# CoffeeHeater.net
KiCad netlist of a schematic drawn in EAGLE
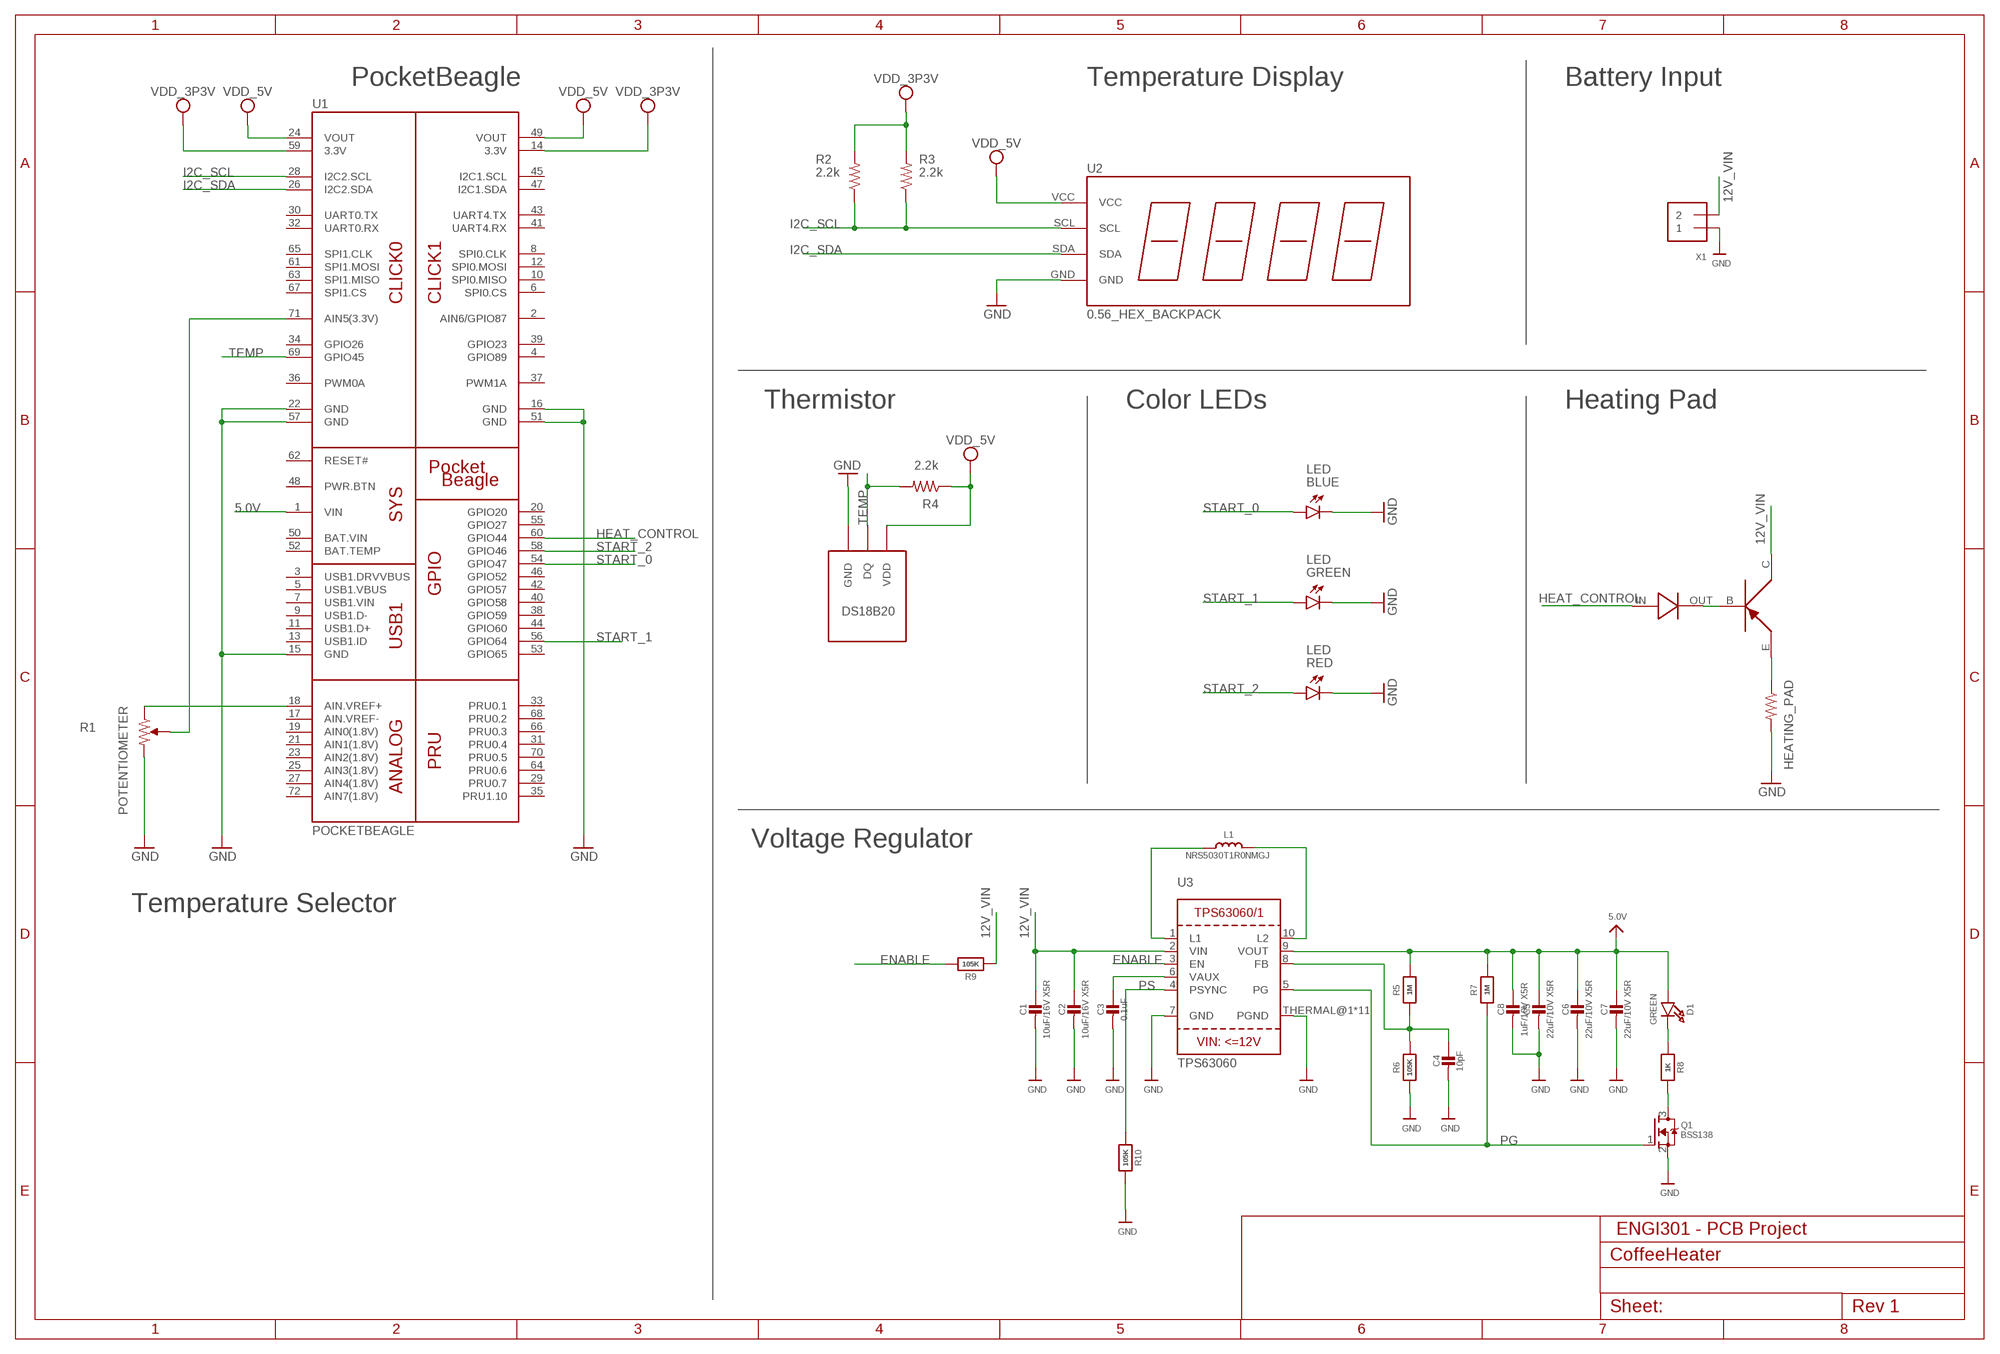
[diagram p0: schematic, sheet 1]

(export (version "E")
  (design (tool "Eeschema 10.0.6"))
  (components
    (comp (ref "BLUE")
      (value "LED")
      (footprint "eagle-import:EIA-STD")
      (libsource (lib "eagle-import") (part "LED"))
    )
    (comp (ref "C1")
      (value "10uF/16V X5R")
      (footprint "eagle-import:0805-NO")
      (libsource (lib "eagle-import") (part "CAP_CERAMIC0805-NOOUTLINE"))
    )
    (comp (ref "C2")
      (value "10uF/16V X5R")
      (footprint "eagle-import:0805-NO")
      (libsource (lib "eagle-import") (part "CAP_CERAMIC0805-NOOUTLINE"))
    )
    (comp (ref "C3")
      (value "0.1uF")
      (footprint "eagle-import:0805-NO")
      (libsource (lib "eagle-import") (part "CAP_CERAMIC0805-NOOUTLINE"))
    )
    (comp (ref "C4")
      (value "10pF")
      (footprint "eagle-import:0805-NO")
      (libsource (lib "eagle-import") (part "CAP_CERAMIC0805-NOOUTLINE"))
    )
    (comp (ref "C5")
      (value "22uF/10V X5R")
      (footprint "eagle-import:0805-NO")
      (libsource (lib "eagle-import") (part "CAP_CERAMIC0805-NOOUTLINE"))
    )
    (comp (ref "C6")
      (value "22uF/10V X5R")
      (footprint "eagle-import:0805-NO")
      (libsource (lib "eagle-import") (part "CAP_CERAMIC0805-NOOUTLINE"))
    )
    (comp (ref "C7")
      (value "22uF/10V X5R")
      (footprint "eagle-import:0805-NO")
      (libsource (lib "eagle-import") (part "CAP_CERAMIC0805-NOOUTLINE"))
    )
    (comp (ref "C8")
      (value "1uF/10V X5R")
      (footprint "eagle-import:0805-NO")
      (libsource (lib "eagle-import") (part "CAP_CERAMIC0805-NOOUTLINE"))
    )
    (comp (ref "D1")
      (value "GREEN")
      (footprint "eagle-import:CHIPLED_0805_NOOUTLINE")
      (libsource (lib "eagle-import") (part "LED0805_NOOUTLINE"))
    )
    (comp (ref "GREEN")
      (value "LED")
      (footprint "eagle-import:EIA-STD")
      (libsource (lib "eagle-import") (part "LED"))
    )
    (comp (ref "L1")
      (value "NRS5030T1R0NMGJ")
      (footprint "eagle-import:INDUCTOR_5X5MM_TDK_VLC5045")
      (libsource (lib "eagle-import") (part "INDUCTORTDK_VLC5045"))
    )
    (comp (ref "Q1")
      (value "BSS138")
      (footprint "eagle-import:SOT23-WIDE")
      (libsource (lib "eagle-import") (part "MOSFET-NWIDE"))
    )
    (comp (ref "R1")
      (value "POTENTIOMETER")
      (footprint "eagle-import:POT-PO90S")
      (libsource (lib "eagle-import") (part "POTENTIOMETER"))
    )
    (comp (ref "R2")
      (value "2.2k")
      (footprint "eagle-import:R0603")
      (libsource (lib "eagle-import") (part "R_R0603"))
    )
    (comp (ref "R3")
      (value "2.2k")
      (footprint "eagle-import:R0603")
      (libsource (lib "eagle-import") (part "R_R0603"))
    )
    (comp (ref "R4")
      (value "2.2k")
      (footprint "eagle-import:R0603")
      (libsource (lib "eagle-import") (part "R_R0603"))
    )
    (comp (ref "R5")
      (value "1M")
      (footprint "eagle-import:0805-NO")
      (libsource (lib "eagle-import") (part "RESISTOR0805_NOOUTLINE"))
    )
    (comp (ref "R6")
      (value "105K")
      (footprint "eagle-import:0805-NO")
      (libsource (lib "eagle-import") (part "RESISTOR0805_NOOUTLINE"))
    )
    (comp (ref "R7")
      (value "1M")
      (footprint "eagle-import:0805-NO")
      (libsource (lib "eagle-import") (part "RESISTOR0805_NOOUTLINE"))
    )
    (comp (ref "R8")
      (value "1K")
      (footprint "eagle-import:0805-NO")
      (libsource (lib "eagle-import") (part "RESISTOR0805_NOOUTLINE"))
    )
    (comp (ref "R9")
      (value "105K")
      (footprint "eagle-import:0805-NO")
      (libsource (lib "eagle-import") (part "RESISTOR0805_NOOUTLINE"))
    )
    (comp (ref "R10")
      (value "105K")
      (footprint "eagle-import:0805-NO")
      (libsource (lib "eagle-import") (part "RESISTOR0805_NOOUTLINE"))
    )
    (comp (ref "RED")
      (value "LED")
      (footprint "eagle-import:EIA-STD")
      (libsource (lib "eagle-import") (part "LED"))
    )
    (comp (ref "U$1")
      (value "DS18B20_TEMP_SENSOR")
      (footprint "eagle-import:DS18B20_TEMP_SENSOR")
      (libsource (lib "eagle-import") (part "DS18B20_TEMP_SENSOR"))
    )
    (comp (ref "U$2")
      (value "TIP32C_TRANSISTOR")
      (footprint "eagle-import:TIP32C_TRANSISTOR")
      (libsource (lib "eagle-import") (part "TIP32C_TRANSISTOR"))
    )
    (comp (ref "U$3")
      (value "DIODE")
      (footprint "eagle-import:DIODE")
      (libsource (lib "eagle-import") (part "DIODE"))
    )
    (comp (ref "U$4")
      (value "HEATING_PAD")
      (footprint "eagle-import:HEATING_PAD")
      (libsource (lib "eagle-import") (part "HEATING_PAD"))
    )
    (comp (ref "U1")
      (value "POCKETBEAGLE")
      (footprint "eagle-import:POCKETBEAGLE")
      (libsource (lib "eagle-import") (part "POCKETBEAGLE"))
    )
    (comp (ref "U2")
      (value "0.56_HEX_BACKPACK")
      (footprint "eagle-import:0.56_HEX_BACKPACK")
      (libsource (lib "eagle-import") (part "0.56_HEX_BACKPACK"))
    )
    (comp (ref "U3")
      (value "TPS63060")
      (footprint "eagle-import:PWSON-N10")
      (libsource (lib "eagle-import") (part "VREG_TPS63060/1"))
    )
    (comp (ref "X1")
      (value "TERMBLOCK_1X2")
      (footprint "eagle-import:TERMBLOCK_1X2-3.5MM")
      (libsource (lib "eagle-import") (part "TERMBLOCK_1X2"))
    )
  )
  (nets
    (net (code "1") (name "/12V_VIN") (class "Default")
      (node (ref "C1") (pin "1") (pinfunction "1_1") (pintype "passive"))
      (node (ref "C2") (pin "1") (pinfunction "1_1") (pintype "passive"))
      (node (ref "R9") (pin "1") (pinfunction "1_1") (pintype "passive"))
      (node (ref "U$2") (pin "C") (pinfunction "C_C") (pintype "bidirectional"))
      (node (ref "U3") (pin "2") (pinfunction "VIN_2") (pintype "power_in"))
      (node (ref "X1") (pin "2") (pinfunction "2_2") (pintype "passive"))
    )
    (net (code "2") (name "/BAT.VIN") (class "Default")
      (node (ref "U1") (pin "50") (pinfunction "BAT.VIN_50") (pintype "power_in"))
    )
    (net (code "3") (name "/ENABLE") (class "Default")
      (node (ref "R9") (pin "2") (pinfunction "2_2") (pintype "passive"))
      (node (ref "U3") (pin "3") (pinfunction "EN_3") (pintype "input"))
    )
    (net (code "4") (name "/HEAT_CONTROL") (class "Default")
      (node (ref "U$3") (pin "IN") (pinfunction "IN_IN") (pintype "bidirectional"))
      (node (ref "U1") (pin "60") (pinfunction "GPIO44_60") (pintype "bidirectional"))
    )
    (net (code "5") (name "/I2C_SCL") (class "Default")
      (node (ref "R2") (pin "1") (pinfunction "1_1") (pintype "passive"))
      (node (ref "R3") (pin "1") (pinfunction "1_1") (pintype "passive"))
      (node (ref "U1") (pin "28") (pinfunction "I2C2.SCL_28") (pintype "bidirectional"))
      (node (ref "U2") (pin "SCL") (pinfunction "SCL_SCL") (pintype "bidirectional"))
    )
    (net (code "6") (name "/I2C_SDA") (class "Default")
      (node (ref "U1") (pin "26") (pinfunction "I2C2.SDA_26") (pintype "bidirectional"))
      (node (ref "U2") (pin "SDA") (pinfunction "SDA_SDA") (pintype "bidirectional"))
    )
    (net (code "7") (name "/PG") (class "Default")
      (node (ref "Q1") (pin "1") (pinfunction "G_1") (pintype "bidirectional"))
      (node (ref "R7") (pin "1") (pinfunction "1_1") (pintype "passive"))
      (node (ref "U3") (pin "5") (pinfunction "PG_5") (pintype "open_collector"))
    )
    (net (code "8") (name "/PS") (class "Default")
      (node (ref "R10") (pin "1") (pinfunction "1_1") (pintype "passive"))
      (node (ref "U3") (pin "4") (pinfunction "PSYNC_4") (pintype "input"))
    )
    (net (code "9") (name "/START_0") (class "Default")
      (node (ref "BLUE") (pin "P$1") (pinfunction "A_P$1") (pintype "passive"))
      (node (ref "U1") (pin "54") (pinfunction "GPIO47_54") (pintype "bidirectional"))
    )
    (net (code "10") (name "/START_1") (class "Default")
      (node (ref "GREEN") (pin "P$1") (pinfunction "A_P$1") (pintype "passive"))
      (node (ref "U1") (pin "56") (pinfunction "GPIO64_56") (pintype "bidirectional"))
    )
    (net (code "11") (name "/START_2") (class "Default")
      (node (ref "RED") (pin "P$1") (pinfunction "A_P$1") (pintype "passive"))
      (node (ref "U1") (pin "58") (pinfunction "GPIO46_58") (pintype "bidirectional"))
    )
    (net (code "12") (name "/TEMP") (class "Default")
      (node (ref "R4") (pin "2") (pinfunction "2_2") (pintype "passive"))
      (node (ref "U$1") (pin "DQ") (pinfunction "DQ_DQ") (pintype "bidirectional"))
      (node (ref "U1") (pin "69") (pinfunction "GPIO45_69") (pintype "bidirectional"))
    )
    (net (code "13") (name "5.0V") (class "Default")
      (node (ref "C5") (pin "1") (pinfunction "1_1") (pintype "passive"))
      (node (ref "C6") (pin "1") (pinfunction "1_1") (pintype "passive"))
      (node (ref "C7") (pin "1") (pinfunction "1_1") (pintype "passive"))
      (node (ref "C8") (pin "1") (pinfunction "1_1") (pintype "passive"))
      (node (ref "D1") (pin "A") (pinfunction "A_A") (pintype "passive"))
      (node (ref "R5") (pin "2") (pinfunction "2_2") (pintype "passive"))
      (node (ref "R7") (pin "2") (pinfunction "2_2") (pintype "passive"))
      (node (ref "U1") (pin "1") (pinfunction "VIN_1") (pintype "power_in"))
      (node (ref "U3") (pin "9") (pinfunction "VOUT_9") (pintype "power_in"))
    )
    (net (code "14") (name "GND") (class "Default")
      (node (ref "BLUE") (pin "P$2") (pinfunction "C_P$2") (pintype "passive"))
      (node (ref "C1") (pin "2") (pinfunction "2_2") (pintype "passive"))
      (node (ref "C2") (pin "2") (pinfunction "2_2") (pintype "passive"))
      (node (ref "C3") (pin "2") (pinfunction "2_2") (pintype "passive"))
      (node (ref "C4") (pin "2") (pinfunction "2_2") (pintype "passive"))
      (node (ref "C5") (pin "2") (pinfunction "2_2") (pintype "passive"))
      (node (ref "C6") (pin "2") (pinfunction "2_2") (pintype "passive"))
      (node (ref "C7") (pin "2") (pinfunction "2_2") (pintype "passive"))
      (node (ref "C8") (pin "2") (pinfunction "2_2") (pintype "passive"))
      (node (ref "GREEN") (pin "P$2") (pinfunction "C_P$2") (pintype "passive"))
      (node (ref "Q1") (pin "2") (pinfunction "S_2") (pintype "bidirectional"))
      (node (ref "R1") (pin "CW") (pinfunction "CW_CW") (pintype "passive"))
      (node (ref "R10") (pin "2") (pinfunction "2_2") (pintype "passive"))
      (node (ref "R6") (pin "1") (pinfunction "1_1") (pintype "passive"))
      (node (ref "RED") (pin "P$2") (pinfunction "C_P$2") (pintype "passive"))
      (node (ref "U$1") (pin "GND") (pinfunction "GND_GND") (pintype "bidirectional"))
      (node (ref "U$4") (pin "GND") (pinfunction "2_GND") (pintype "passive"))
      (node (ref "U1") (pin "15") (pinfunction "GND_15") (pintype "bidirectional"))
      (node (ref "U1") (pin "16") (pinfunction "GND_16") (pintype "power_in"))
      (node (ref "U1") (pin "22") (pinfunction "GND_22") (pintype "power_in"))
      (node (ref "U1") (pin "51") (pinfunction "GND_51") (pintype "power_in"))
      (node (ref "U1") (pin "57") (pinfunction "GND_57") (pintype "power_in"))
      (node (ref "U2") (pin "GND") (pinfunction "GND_GND") (pintype "bidirectional"))
      (node (ref "U3") (pin "7") (pinfunction "GND_7") (pintype "power_in"))
      (node (ref "U3") (pin "THERMAL@1") (pinfunction "PGND_THERMAL@1") (pintype "power_in"))
      (node (ref "U3") (pin "THERMAL@10") (pinfunction "PGND_THERMAL@10") (pintype "power_in"))
      (node (ref "U3") (pin "THERMAL@11") (pinfunction "PGND_THERMAL@11") (pintype "power_in"))
      (node (ref "U3") (pin "THERMAL@12") (pinfunction "PGND_THERMAL@12") (pintype "power_in"))
      (node (ref "U3") (pin "THERMAL@13") (pinfunction "PGND_THERMAL@13") (pintype "power_in"))
      (node (ref "U3") (pin "THERMAL@14") (pinfunction "PGND_THERMAL@14") (pintype "power_in"))
      (node (ref "U3") (pin "THERMAL@5") (pinfunction "PGND_THERMAL@5") (pintype "power_in"))
      (node (ref "U3") (pin "THERMAL@6") (pinfunction "PGND_THERMAL@6") (pintype "power_in"))
      (node (ref "U3") (pin "THERMAL@7") (pinfunction "PGND_THERMAL@7") (pintype "power_in"))
      (node (ref "U3") (pin "THERMAL@8") (pinfunction "PGND_THERMAL@8") (pintype "power_in"))
      (node (ref "U3") (pin "THERMAL@9") (pinfunction "PGND_THERMAL@9") (pintype "power_in"))
      (node (ref "X1") (pin "1") (pinfunction "1_1") (pintype "passive"))
    )
    (net (code "15") (name "Net-(D1-PadC)") (class "Default")
      (node (ref "D1") (pin "C") (pinfunction "C_C") (pintype "passive"))
      (node (ref "R8") (pin "1") (pinfunction "1_1") (pintype "passive"))
    )
    (net (code "16") (name "Net-(L1-1)") (class "Default")
      (node (ref "L1") (pin "P$1") (pinfunction "1_P$1") (pintype "passive"))
      (node (ref "U3") (pin "1") (pinfunction "L1_1") (pintype "input"))
    )
    (net (code "17") (name "Net-(L1-2)") (class "Default")
      (node (ref "L1") (pin "P$2") (pinfunction "2_P$2") (pintype "passive"))
      (node (ref "U3") (pin "10") (pinfunction "L2_10") (pintype "input"))
    )
    (net (code "18") (name "Net-(Q1-D)") (class "Default")
      (node (ref "Q1") (pin "3") (pinfunction "D_3") (pintype "bidirectional"))
      (node (ref "R8") (pin "2") (pinfunction "2_2") (pintype "passive"))
    )
    (net (code "19") (name "Net-(U$2-PadB)") (class "Default")
      (node (ref "U$2") (pin "B") (pinfunction "B_B") (pintype "bidirectional"))
      (node (ref "U$3") (pin "OUT") (pinfunction "OUT_OUT") (pintype "bidirectional"))
    )
    (net (code "20") (name "Net-(U$4-1)") (class "Default")
      (node (ref "U$2") (pin "E") (pinfunction "E_E") (pintype "bidirectional"))
      (node (ref "U$4") (pin "VDD") (pinfunction "1_VDD") (pintype "passive"))
    )
    (net (code "21") (name "Net-(U1-AIN.VREF+)") (class "Default")
      (node (ref "R1") (pin "CCW") (pinfunction "CCW_CCW") (pintype "passive"))
      (node (ref "U1") (pin "18") (pinfunction "AIN.VREF+_18") (pintype "input"))
    )
    (net (code "22") (name "Net-(U1-AIN5(3.3V))") (class "Default")
      (node (ref "R1") (pin "S") (pinfunction "S_S") (pintype "bidirectional"))
      (node (ref "U1") (pin "71") (pinfunction "AIN5(3.3V)_71") (pintype "bidirectional"))
    )
    (net (code "23") (name "Net-(U3-FB)") (class "Default")
      (node (ref "C4") (pin "1") (pinfunction "1_1") (pintype "passive"))
      (node (ref "R5") (pin "1") (pinfunction "1_1") (pintype "passive"))
      (node (ref "R6") (pin "2") (pinfunction "2_2") (pintype "passive"))
      (node (ref "U3") (pin "8") (pinfunction "FB_8") (pintype "input"))
    )
    (net (code "24") (name "Net-(U3-VAUX)") (class "Default")
      (node (ref "C3") (pin "1") (pinfunction "1_1") (pintype "passive"))
      (node (ref "U3") (pin "6") (pinfunction "VAUX_6") (pintype "passive"))
    )
    (net (code "25") (name "VDD_3P3V") (class "Default")
      (node (ref "R2") (pin "2") (pinfunction "2_2") (pintype "passive"))
      (node (ref "R3") (pin "2") (pinfunction "2_2") (pintype "passive"))
      (node (ref "U1") (pin "14") (pinfunction "3.3V_14") (pintype "power_in"))
      (node (ref "U1") (pin "59") (pinfunction "3.3V_59") (pintype "power_in"))
    )
    (net (code "26") (name "VDD_5V") (class "Default")
      (node (ref "R4") (pin "1") (pinfunction "1_1") (pintype "passive"))
      (node (ref "U$1") (pin "VDD") (pinfunction "VDD_VDD") (pintype "bidirectional"))
      (node (ref "U1") (pin "24") (pinfunction "VOUT_24") (pintype "power_in"))
      (node (ref "U1") (pin "49") (pinfunction "VOUT_49") (pintype "power_in"))
      (node (ref "U2") (pin "VCC") (pinfunction "VCC_VCC") (pintype "power_in"))
    )
    (net (code "27") (name "unconnected-(U1-AIN.VREF--Pad17)") (class "Default")
      (node (ref "U1") (pin "17") (pinfunction "AIN.VREF-_17") (pintype "input"))
    )
    (net (code "28") (name "unconnected-(U1-AIN0(1.8V)-Pad19)") (class "Default")
      (node (ref "U1") (pin "19") (pinfunction "AIN0(1.8V)_19") (pintype "input"))
    )
    (net (code "29") (name "unconnected-(U1-AIN1(1.8V)-Pad21)") (class "Default")
      (node (ref "U1") (pin "21") (pinfunction "AIN1(1.8V)_21") (pintype "input"))
    )
    (net (code "30") (name "unconnected-(U1-AIN2(1.8V)-Pad23)") (class "Default")
      (node (ref "U1") (pin "23") (pinfunction "AIN2(1.8V)_23") (pintype "input"))
    )
    (net (code "31") (name "unconnected-(U1-AIN3(1.8V)-Pad25)") (class "Default")
      (node (ref "U1") (pin "25") (pinfunction "AIN3(1.8V)_25") (pintype "input"))
    )
    (net (code "32") (name "unconnected-(U1-AIN4(1.8V)-Pad27)") (class "Default")
      (node (ref "U1") (pin "27") (pinfunction "AIN4(1.8V)_27") (pintype "input"))
    )
    (net (code "33") (name "unconnected-(U1-AIN6{slash}GPIO87-Pad2)") (class "Default")
      (node (ref "U1") (pin "2") (pinfunction "AIN6/GPIO87_2") (pintype "bidirectional"))
    )
    (net (code "34") (name "unconnected-(U1-AIN7(1.8V)-Pad72)") (class "Default")
      (node (ref "U1") (pin "72") (pinfunction "AIN7(1.8V)_72") (pintype "input"))
    )
    (net (code "35") (name "unconnected-(U1-BAT.TEMP-Pad52)") (class "Default")
      (node (ref "U1") (pin "52") (pinfunction "BAT.TEMP_52") (pintype "input"))
    )
    (net (code "36") (name "unconnected-(U1-GPIO20-Pad20)") (class "Default")
      (node (ref "U1") (pin "20") (pinfunction "GPIO20_20") (pintype "bidirectional"))
    )
    (net (code "37") (name "unconnected-(U1-GPIO23-Pad39)") (class "Default")
      (node (ref "U1") (pin "39") (pinfunction "GPIO23_39") (pintype "bidirectional"))
    )
    (net (code "38") (name "unconnected-(U1-GPIO26-Pad34)") (class "Default")
      (node (ref "U1") (pin "34") (pinfunction "GPIO26_34") (pintype "bidirectional"))
    )
    (net (code "39") (name "unconnected-(U1-GPIO27-Pad55)") (class "Default")
      (node (ref "U1") (pin "55") (pinfunction "GPIO27_55") (pintype "bidirectional"))
    )
    (net (code "40") (name "unconnected-(U1-GPIO52-Pad46)") (class "Default")
      (node (ref "U1") (pin "46") (pinfunction "GPIO52_46") (pintype "bidirectional"))
    )
    (net (code "41") (name "unconnected-(U1-GPIO57-Pad42)") (class "Default")
      (node (ref "U1") (pin "42") (pinfunction "GPIO57_42") (pintype "bidirectional"))
    )
    (net (code "42") (name "unconnected-(U1-GPIO58-Pad40)") (class "Default")
      (node (ref "U1") (pin "40") (pinfunction "GPIO58_40") (pintype "bidirectional"))
    )
    (net (code "43") (name "unconnected-(U1-GPIO59-Pad38)") (class "Default")
      (node (ref "U1") (pin "38") (pinfunction "GPIO59_38") (pintype "bidirectional"))
    )
    (net (code "44") (name "unconnected-(U1-GPIO60-Pad44)") (class "Default")
      (node (ref "U1") (pin "44") (pinfunction "GPIO60_44") (pintype "bidirectional"))
    )
    (net (code "45") (name "unconnected-(U1-GPIO65-Pad53)") (class "Default")
      (node (ref "U1") (pin "53") (pinfunction "GPIO65_53") (pintype "bidirectional"))
    )
    (net (code "46") (name "unconnected-(U1-GPIO89-Pad4)") (class "Default")
      (node (ref "U1") (pin "4") (pinfunction "GPIO89_4") (pintype "bidirectional"))
    )
    (net (code "47") (name "unconnected-(U1-I2C1.SCL-Pad45)") (class "Default")
      (node (ref "U1") (pin "45") (pinfunction "I2C1.SCL_45") (pintype "bidirectional"))
    )
    (net (code "48") (name "unconnected-(U1-I2C1.SDA-Pad47)") (class "Default")
      (node (ref "U1") (pin "47") (pinfunction "I2C1.SDA_47") (pintype "bidirectional"))
    )
    (net (code "49") (name "unconnected-(U1-PRU0.1-Pad33)") (class "Default")
      (node (ref "U1") (pin "33") (pinfunction "PRU0.1_33") (pintype "bidirectional"))
    )
    (net (code "50") (name "unconnected-(U1-PRU0.2-Pad68)") (class "Default")
      (node (ref "U1") (pin "68") (pinfunction "PRU0.2_68") (pintype "bidirectional"))
    )
    (net (code "51") (name "unconnected-(U1-PRU0.3-Pad66)") (class "Default")
      (node (ref "U1") (pin "66") (pinfunction "PRU0.3_66") (pintype "bidirectional"))
    )
    (net (code "52") (name "unconnected-(U1-PRU0.4-Pad31)") (class "Default")
      (node (ref "U1") (pin "31") (pinfunction "PRU0.4_31") (pintype "bidirectional"))
    )
    (net (code "53") (name "unconnected-(U1-PRU0.5-Pad70)") (class "Default")
      (node (ref "U1") (pin "70") (pinfunction "PRU0.5_70") (pintype "bidirectional"))
    )
    (net (code "54") (name "unconnected-(U1-PRU0.6-Pad64)") (class "Default")
      (node (ref "U1") (pin "64") (pinfunction "PRU0.6_64") (pintype "bidirectional"))
    )
    (net (code "55") (name "unconnected-(U1-PRU0.7-Pad29)") (class "Default")
      (node (ref "U1") (pin "29") (pinfunction "PRU0.7_29") (pintype "bidirectional"))
    )
    (net (code "56") (name "unconnected-(U1-PRU1.10-Pad35)") (class "Default")
      (node (ref "U1") (pin "35") (pinfunction "PRU1.10_35") (pintype "bidirectional"))
    )
    (net (code "57") (name "unconnected-(U1-PWM0A-Pad36)") (class "Default")
      (node (ref "U1") (pin "36") (pinfunction "PWM0A_36") (pintype "bidirectional"))
    )
    (net (code "58") (name "unconnected-(U1-PWM1A-Pad37)") (class "Default")
      (node (ref "U1") (pin "37") (pinfunction "PWM1A_37") (pintype "bidirectional"))
    )
    (net (code "59") (name "unconnected-(U1-PWR.BTN-Pad48)") (class "Default")
      (node (ref "U1") (pin "48") (pinfunction "PWR.BTN_48") (pintype "input"))
    )
    (net (code "60") (name "unconnected-(U1-RESET#-Pad62)") (class "Default")
      (node (ref "U1") (pin "62") (pinfunction "RESET#_62") (pintype "input"))
    )
    (net (code "61") (name "unconnected-(U1-SPI0.CLK-Pad8)") (class "Default")
      (node (ref "U1") (pin "8") (pinfunction "SPI0.CLK_8") (pintype "bidirectional"))
    )
    (net (code "62") (name "unconnected-(U1-SPI0.CS-Pad6)") (class "Default")
      (node (ref "U1") (pin "6") (pinfunction "SPI0.CS_6") (pintype "bidirectional"))
    )
    (net (code "63") (name "unconnected-(U1-SPI0.MISO-Pad10)") (class "Default")
      (node (ref "U1") (pin "10") (pinfunction "SPI0.MISO_10") (pintype "bidirectional"))
    )
    (net (code "64") (name "unconnected-(U1-SPI0.MOSI-Pad12)") (class "Default")
      (node (ref "U1") (pin "12") (pinfunction "SPI0.MOSI_12") (pintype "bidirectional"))
    )
    (net (code "65") (name "unconnected-(U1-SPI1.CLK-Pad65)") (class "Default")
      (node (ref "U1") (pin "65") (pinfunction "SPI1.CLK_65") (pintype "bidirectional"))
    )
    (net (code "66") (name "unconnected-(U1-SPI1.CS-Pad67)") (class "Default")
      (node (ref "U1") (pin "67") (pinfunction "SPI1.CS_67") (pintype "bidirectional"))
    )
    (net (code "67") (name "unconnected-(U1-SPI1.MISO-Pad63)") (class "Default")
      (node (ref "U1") (pin "63") (pinfunction "SPI1.MISO_63") (pintype "bidirectional"))
    )
    (net (code "68") (name "unconnected-(U1-SPI1.MOSI-Pad61)") (class "Default")
      (node (ref "U1") (pin "61") (pinfunction "SPI1.MOSI_61") (pintype "bidirectional"))
    )
    (net (code "69") (name "unconnected-(U1-UART0.RX-Pad32)") (class "Default")
      (node (ref "U1") (pin "32") (pinfunction "UART0.RX_32") (pintype "bidirectional"))
    )
    (net (code "70") (name "unconnected-(U1-UART0.TX-Pad30)") (class "Default")
      (node (ref "U1") (pin "30") (pinfunction "UART0.TX_30") (pintype "bidirectional"))
    )
    (net (code "71") (name "unconnected-(U1-UART4.RX-Pad41)") (class "Default")
      (node (ref "U1") (pin "41") (pinfunction "UART4.RX_41") (pintype "bidirectional"))
    )
    (net (code "72") (name "unconnected-(U1-UART4.TX-Pad43)") (class "Default")
      (node (ref "U1") (pin "43") (pinfunction "UART4.TX_43") (pintype "bidirectional"))
    )
    (net (code "73") (name "unconnected-(U1-USB1.D+-Pad11)") (class "Default")
      (node (ref "U1") (pin "11") (pinfunction "USB1.D+_11") (pintype "bidirectional"))
    )
    (net (code "74") (name "unconnected-(U1-USB1.D--Pad9)") (class "Default")
      (node (ref "U1") (pin "9") (pinfunction "USB1.D-_9") (pintype "bidirectional"))
    )
    (net (code "75") (name "unconnected-(U1-USB1.DRVVBUS-Pad3)") (class "Default")
      (node (ref "U1") (pin "3") (pinfunction "USB1.DRVVBUS_3") (pintype "bidirectional"))
    )
    (net (code "76") (name "unconnected-(U1-USB1.ID-Pad13)") (class "Default")
      (node (ref "U1") (pin "13") (pinfunction "USB1.ID_13") (pintype "bidirectional"))
    )
    (net (code "77") (name "unconnected-(U1-USB1.VBUS-Pad5)") (class "Default")
      (node (ref "U1") (pin "5") (pinfunction "USB1.VBUS_5") (pintype "bidirectional"))
    )
    (net (code "78") (name "unconnected-(U1-USB1.VIN-Pad7)") (class "Default")
      (node (ref "U1") (pin "7") (pinfunction "USB1.VIN_7") (pintype "bidirectional"))
    )
  )
)
